# tb_project_ir_blaster2_wemos_revA.net
KiCad netlist of a schematic drawn in EAGLE
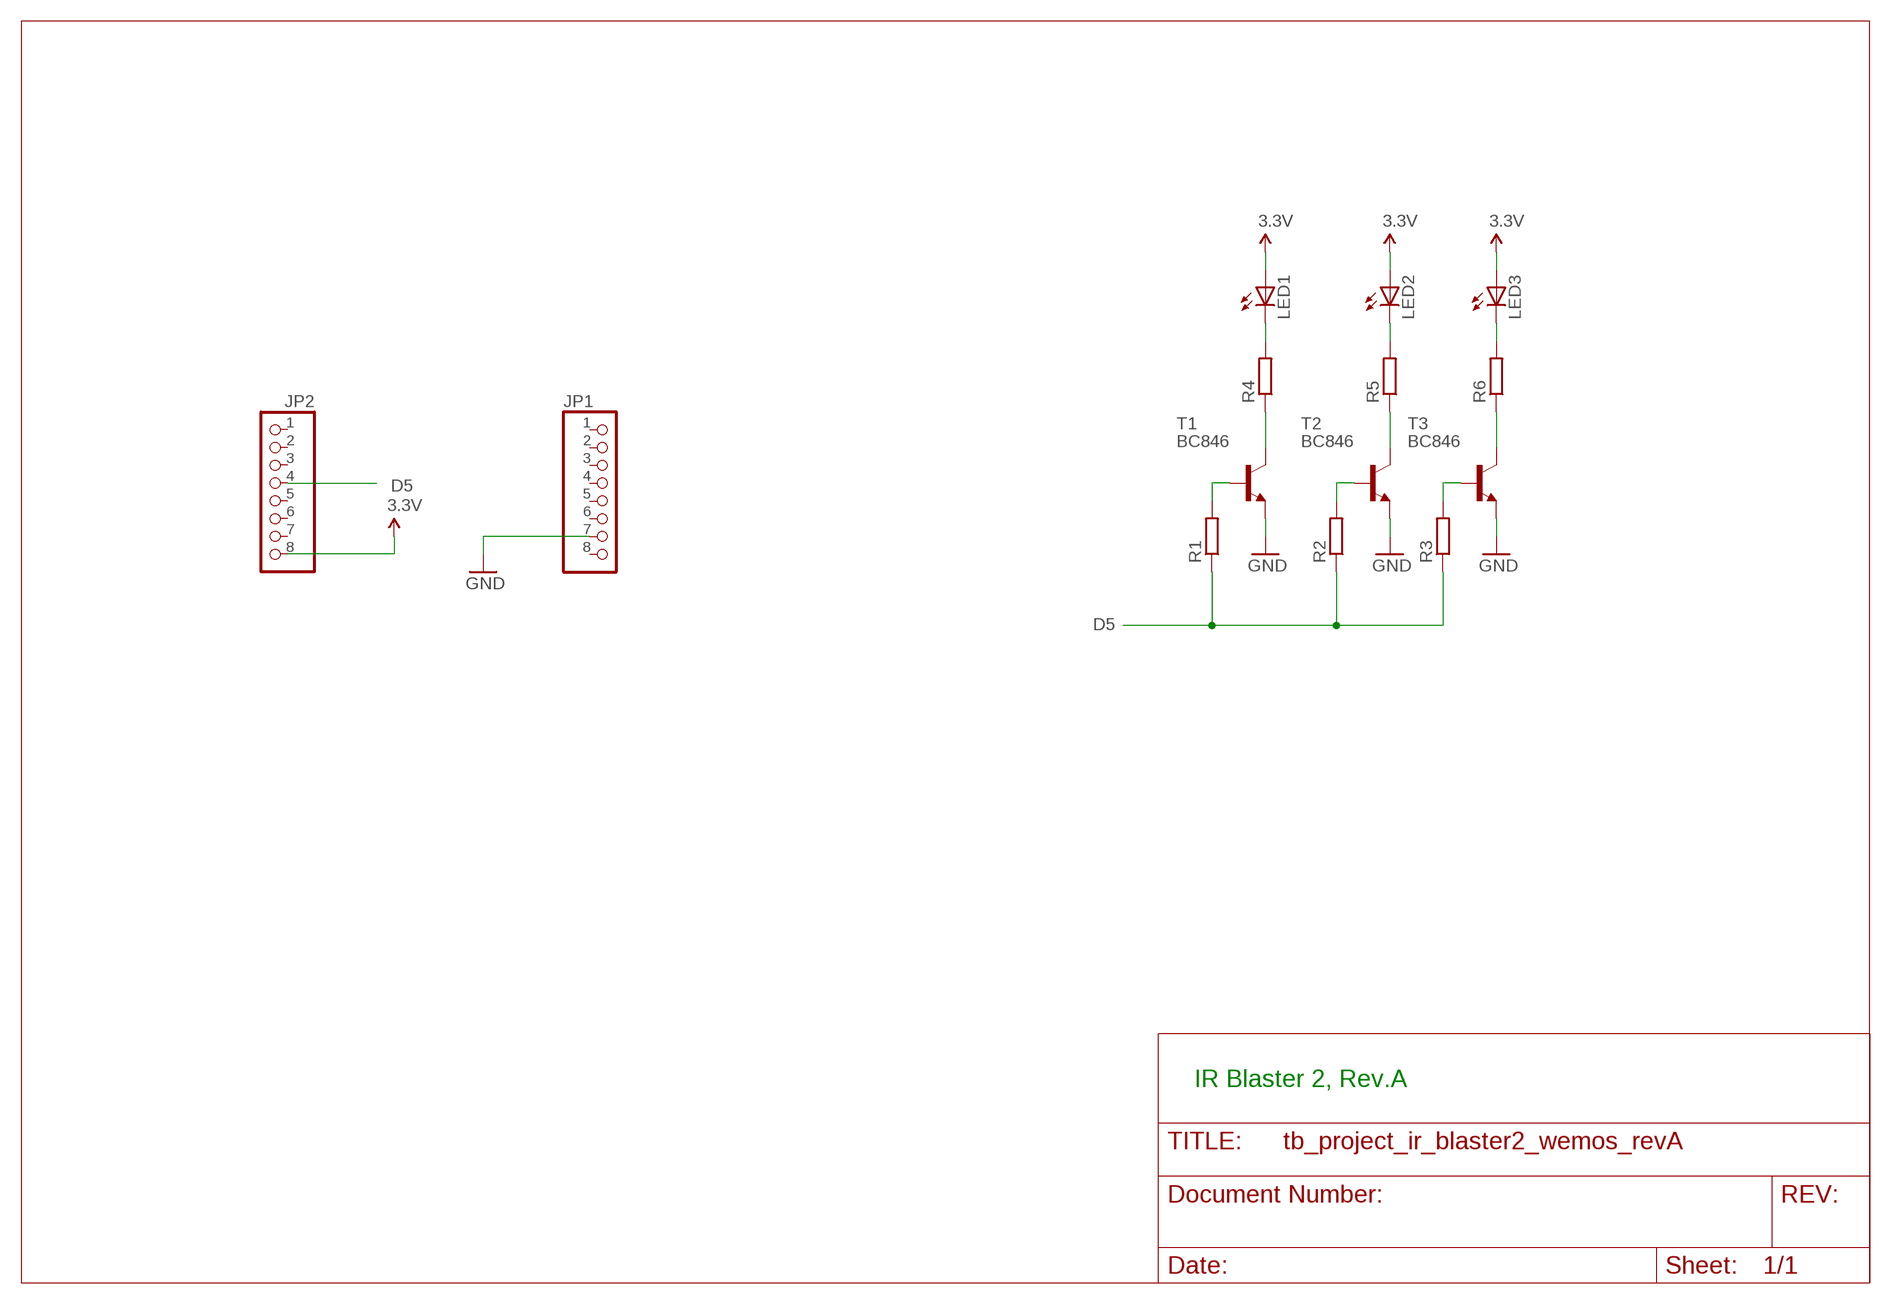
[diagram p0: schematic, sheet 1]

(export (version "E")
  (design (tool "Eeschema 10.0.6"))
  (components
    (comp (ref "JP1")
      (value "PINHD-1X8")
      (footprint "eagle-import:1X08")
      (libsource (lib "eagle-import") (part "PINHD-1X8"))
    )
    (comp (ref "JP2")
      (value "PINHD-1X8")
      (footprint "eagle-import:1X08")
      (libsource (lib "eagle-import") (part "PINHD-1X8"))
    )
    (comp (ref "LED1")
      (value "LED5MM")
      (footprint "eagle-import:LED5MM")
      (libsource (lib "eagle-import") (part "LED5MM"))
    )
    (comp (ref "LED2")
      (value "LED5MM")
      (footprint "eagle-import:LED5MM")
      (libsource (lib "eagle-import") (part "LED5MM"))
    )
    (comp (ref "LED3")
      (value "LED5MM")
      (footprint "eagle-import:LED5MM")
      (libsource (lib "eagle-import") (part "LED5MM"))
    )
    (comp (ref "R1")
      (value "R-EU_R1206")
      (footprint "eagle-import:R1206")
      (libsource (lib "eagle-import") (part "R-EU_R1206"))
    )
    (comp (ref "R2")
      (value "R-EU_R1206")
      (footprint "eagle-import:R1206")
      (libsource (lib "eagle-import") (part "R-EU_R1206"))
    )
    (comp (ref "R3")
      (value "R-EU_R1206")
      (footprint "eagle-import:R1206")
      (libsource (lib "eagle-import") (part "R-EU_R1206"))
    )
    (comp (ref "R4")
      (value "R-EU_R1206")
      (footprint "eagle-import:R1206")
      (libsource (lib "eagle-import") (part "R-EU_R1206"))
    )
    (comp (ref "R5")
      (value "R-EU_R1206")
      (footprint "eagle-import:R1206")
      (libsource (lib "eagle-import") (part "R-EU_R1206"))
    )
    (comp (ref "R6")
      (value "R-EU_R1206")
      (footprint "eagle-import:R1206")
      (libsource (lib "eagle-import") (part "R-EU_R1206"))
    )
    (comp (ref "T1")
      (value "BC846")
      (footprint "eagle-import:SOT23")
      (libsource (lib "eagle-import") (part "BC846"))
    )
    (comp (ref "T2")
      (value "BC846")
      (footprint "eagle-import:SOT23")
      (libsource (lib "eagle-import") (part "BC846"))
    )
    (comp (ref "T3")
      (value "BC846")
      (footprint "eagle-import:SOT23")
      (libsource (lib "eagle-import") (part "BC846"))
    )
  )
  (nets
    (net (code "1") (name "/D5") (class "Default")
      (node (ref "JP2") (pin "4") (pinfunction "4_4") (pintype "passive"))
      (node (ref "R1") (pin "1") (pinfunction "1_1") (pintype "passive"))
      (node (ref "R2") (pin "1") (pinfunction "1_1") (pintype "passive"))
      (node (ref "R3") (pin "1") (pinfunction "1_1") (pintype "passive"))
    )
    (net (code "2") (name "3.3V") (class "Default")
      (node (ref "JP2") (pin "8") (pinfunction "8_8") (pintype "passive"))
      (node (ref "LED1") (pin "A") (pinfunction "A_A") (pintype "passive"))
      (node (ref "LED2") (pin "A") (pinfunction "A_A") (pintype "passive"))
      (node (ref "LED3") (pin "A") (pinfunction "A_A") (pintype "passive"))
    )
    (net (code "3") (name "GND") (class "Default")
      (node (ref "JP1") (pin "7") (pinfunction "7_7") (pintype "passive"))
      (node (ref "T1") (pin "2") (pinfunction "E_2") (pintype "passive"))
      (node (ref "T2") (pin "2") (pinfunction "E_2") (pintype "passive"))
      (node (ref "T3") (pin "2") (pinfunction "E_2") (pintype "passive"))
    )
    (net (code "4") (name "Net-(LED1-C)") (class "Default")
      (node (ref "LED1") (pin "K") (pinfunction "C_K") (pintype "passive"))
      (node (ref "R4") (pin "2") (pinfunction "2_2") (pintype "passive"))
    )
    (net (code "5") (name "Net-(LED2-C)") (class "Default")
      (node (ref "LED2") (pin "K") (pinfunction "C_K") (pintype "passive"))
      (node (ref "R5") (pin "2") (pinfunction "2_2") (pintype "passive"))
    )
    (net (code "6") (name "Net-(LED3-C)") (class "Default")
      (node (ref "LED3") (pin "K") (pinfunction "C_K") (pintype "passive"))
      (node (ref "R6") (pin "2") (pinfunction "2_2") (pintype "passive"))
    )
    (net (code "7") (name "Net-(T1-B)") (class "Default")
      (node (ref "R1") (pin "2") (pinfunction "2_2") (pintype "passive"))
      (node (ref "T1") (pin "1") (pinfunction "B_1") (pintype "passive"))
    )
    (net (code "8") (name "Net-(T1-C)") (class "Default")
      (node (ref "R4") (pin "1") (pinfunction "1_1") (pintype "passive"))
      (node (ref "T1") (pin "3") (pinfunction "C_3") (pintype "passive"))
    )
    (net (code "9") (name "Net-(T2-B)") (class "Default")
      (node (ref "R2") (pin "2") (pinfunction "2_2") (pintype "passive"))
      (node (ref "T2") (pin "1") (pinfunction "B_1") (pintype "passive"))
    )
    (net (code "10") (name "Net-(T2-C)") (class "Default")
      (node (ref "R5") (pin "1") (pinfunction "1_1") (pintype "passive"))
      (node (ref "T2") (pin "3") (pinfunction "C_3") (pintype "passive"))
    )
    (net (code "11") (name "Net-(T3-B)") (class "Default")
      (node (ref "R3") (pin "2") (pinfunction "2_2") (pintype "passive"))
      (node (ref "T3") (pin "1") (pinfunction "B_1") (pintype "passive"))
    )
    (net (code "12") (name "Net-(T3-C)") (class "Default")
      (node (ref "R6") (pin "1") (pinfunction "1_1") (pintype "passive"))
      (node (ref "T3") (pin "3") (pinfunction "C_3") (pintype "passive"))
    )
    (net (code "13") (name "unconnected-(JP1-Pad1)") (class "Default")
      (node (ref "JP1") (pin "1") (pinfunction "1_1") (pintype "passive"))
    )
    (net (code "14") (name "unconnected-(JP1-Pad2)") (class "Default")
      (node (ref "JP1") (pin "2") (pinfunction "2_2") (pintype "passive"))
    )
    (net (code "15") (name "unconnected-(JP1-Pad3)") (class "Default")
      (node (ref "JP1") (pin "3") (pinfunction "3_3") (pintype "passive"))
    )
    (net (code "16") (name "unconnected-(JP1-Pad4)") (class "Default")
      (node (ref "JP1") (pin "4") (pinfunction "4_4") (pintype "passive"))
    )
    (net (code "17") (name "unconnected-(JP1-Pad5)") (class "Default")
      (node (ref "JP1") (pin "5") (pinfunction "5_5") (pintype "passive"))
    )
    (net (code "18") (name "unconnected-(JP1-Pad6)") (class "Default")
      (node (ref "JP1") (pin "6") (pinfunction "6_6") (pintype "passive"))
    )
    (net (code "19") (name "unconnected-(JP1-Pad8)") (class "Default")
      (node (ref "JP1") (pin "8") (pinfunction "8_8") (pintype "passive"))
    )
    (net (code "20") (name "unconnected-(JP2-Pad1)") (class "Default")
      (node (ref "JP2") (pin "1") (pinfunction "1_1") (pintype "passive"))
    )
    (net (code "21") (name "unconnected-(JP2-Pad2)") (class "Default")
      (node (ref "JP2") (pin "2") (pinfunction "2_2") (pintype "passive"))
    )
    (net (code "22") (name "unconnected-(JP2-Pad3)") (class "Default")
      (node (ref "JP2") (pin "3") (pinfunction "3_3") (pintype "passive"))
    )
    (net (code "23") (name "unconnected-(JP2-Pad5)") (class "Default")
      (node (ref "JP2") (pin "5") (pinfunction "5_5") (pintype "passive"))
    )
    (net (code "24") (name "unconnected-(JP2-Pad6)") (class "Default")
      (node (ref "JP2") (pin "6") (pinfunction "6_6") (pintype "passive"))
    )
    (net (code "25") (name "unconnected-(JP2-Pad7)") (class "Default")
      (node (ref "JP2") (pin "7") (pinfunction "7_7") (pintype "passive"))
    )
  )
)
